# 8Bit_audio_-_7524_axelb.net
KiCad netlist of a schematic drawn in EAGLE
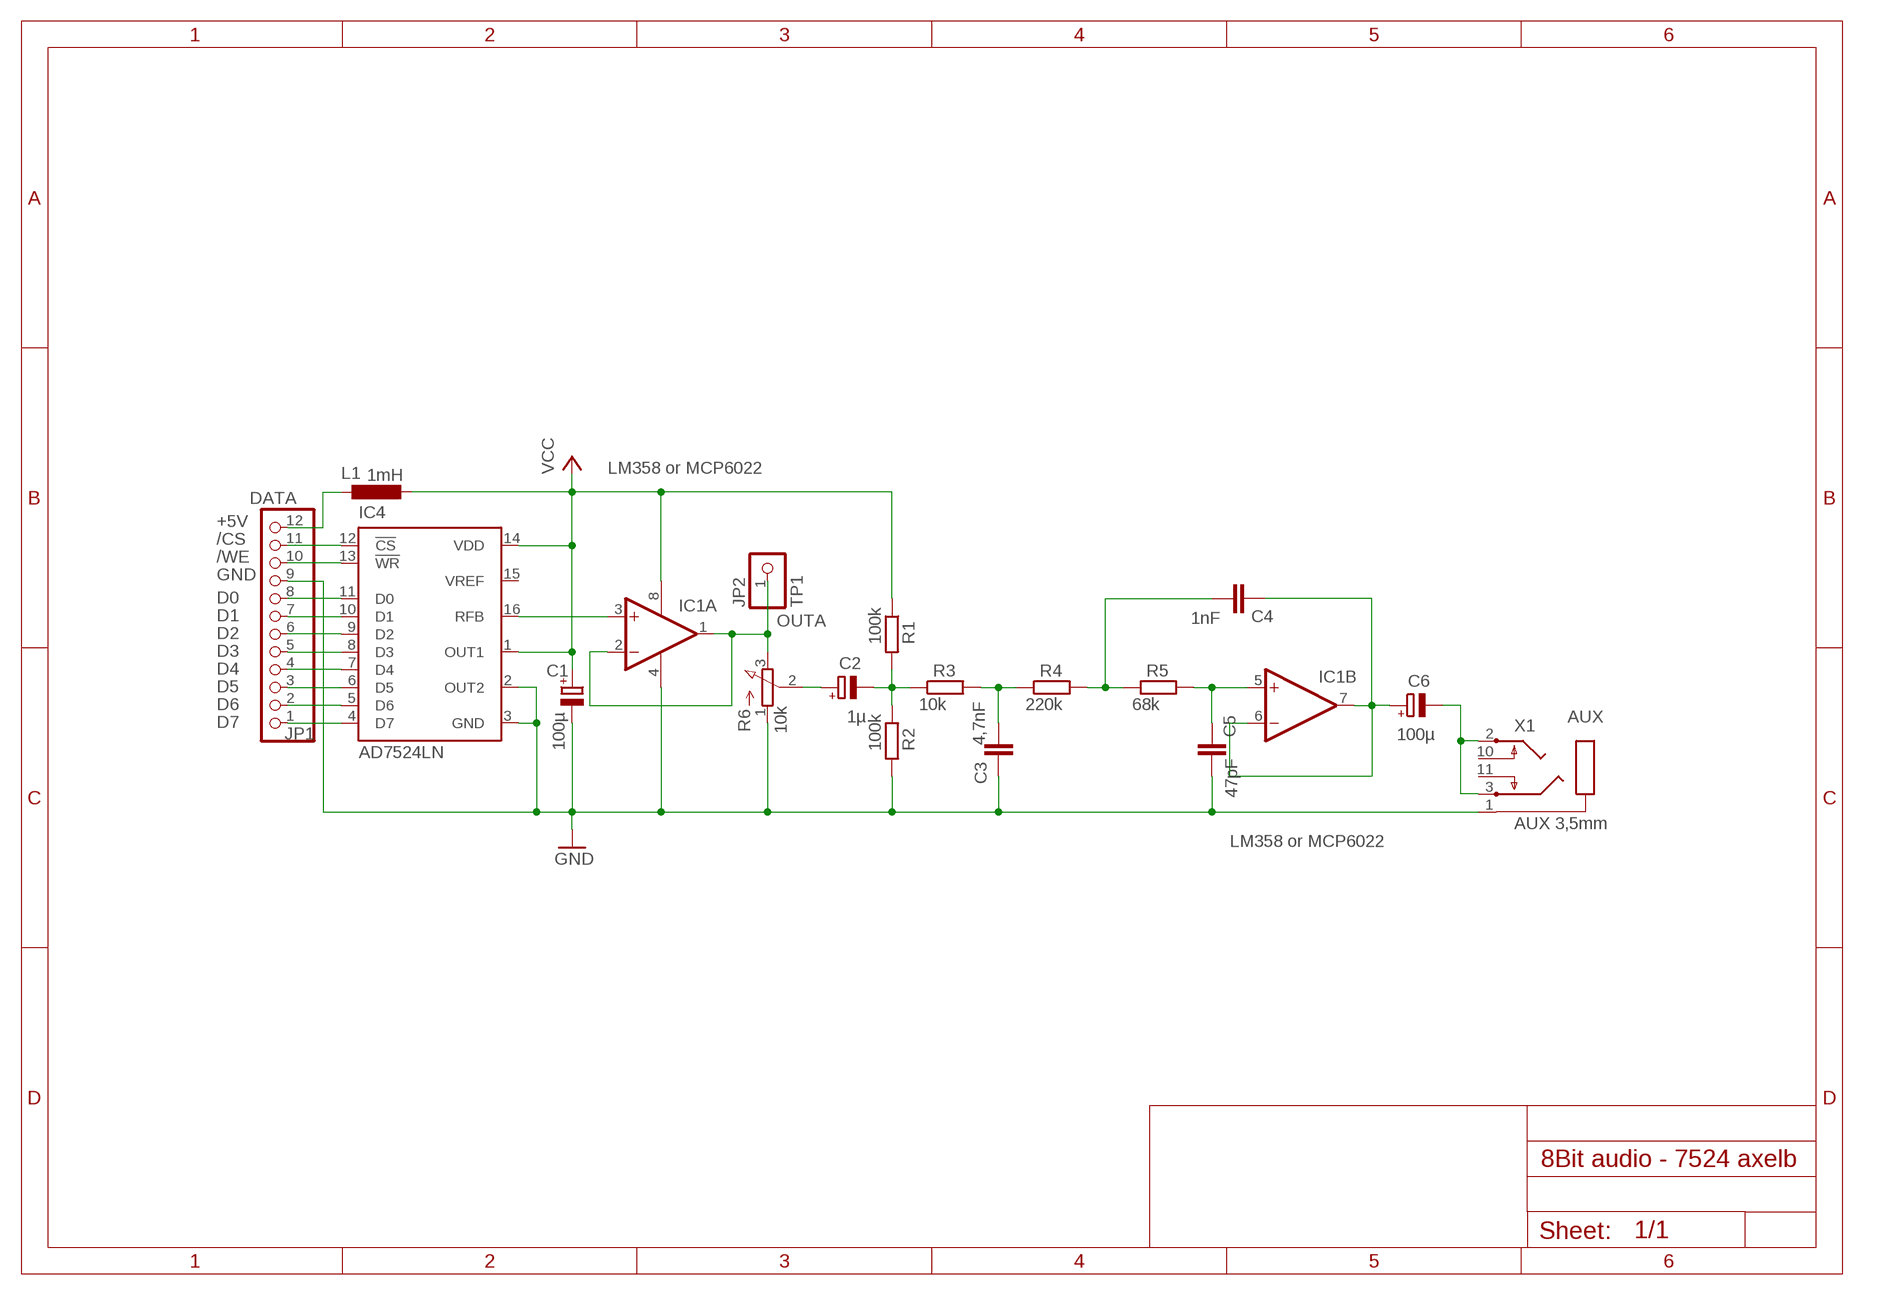
[diagram p0: schematic, sheet 1]

(export (version "E")
  (design (tool "Eeschema 10.0.6"))
  (components
    (comp (ref "C1")
      (value "100µ")
      (footprint "eagle-import:E5-5")
      (libsource (lib "eagle-import") (part "CPOL-EUE5-5"))
    )
    (comp (ref "C2")
      (value "1µ")
      (footprint "eagle-import:E5-5")
      (libsource (lib "eagle-import") (part "CPOL-EUE5-5"))
    )
    (comp (ref "C3")
      (value "4,7nF")
      (footprint "eagle-import:C075-032X103")
      (libsource (lib "eagle-import") (part "C-EU075-032X103"))
    )
    (comp (ref "C4")
      (value "1nF")
      (footprint "eagle-import:C075-032X103")
      (libsource (lib "eagle-import") (part "C-EU075-032X103"))
    )
    (comp (ref "C5")
      (value "47pF")
      (footprint "eagle-import:C075-032X103")
      (libsource (lib "eagle-import") (part "C-EU075-032X103"))
    )
    (comp (ref "C6")
      (value "100µ")
      (footprint "eagle-import:E5-5")
      (libsource (lib "eagle-import") (part "CPOL-EUE5-5"))
    )
    (comp (ref "IC1")
      (value "LM358 or MCP6022")
      (footprint "eagle-import:DIL08")
      (libsource (lib "eagle-import") (part "LM358N"))
    )
    (comp (ref "IC4")
      (value "AD7524LN")
      (footprint "eagle-import:DIL16")
      (fields (field (name "MF") "ALTERA CORPORATION") (field (name "MPN") "AD7524LNZ"))
      (libsource (lib "eagle-import") (part "AD7524NL"))
    )
    (comp (ref "JP1")
      (value "DATA")
      (footprint "eagle-import:1X12")
      (libsource (lib "eagle-import") (part "PINHD-1X12"))
    )
    (comp (ref "JP2")
      (value "TP1")
      (footprint "eagle-import:1X01")
      (libsource (lib "eagle-import") (part "PINHD-1X1"))
    )
    (comp (ref "L1")
      (value "1mH")
      (footprint "eagle-import:0207_10")
      (libsource (lib "eagle-import") (part "L-EU0207/10"))
    )
    (comp (ref "R1")
      (value "100k")
      (footprint "eagle-import:0207_10")
      (libsource (lib "eagle-import") (part "R-EU_0207/10"))
    )
    (comp (ref "R2")
      (value "100k")
      (footprint "eagle-import:0207_10")
      (libsource (lib "eagle-import") (part "R-EU_0207/10"))
    )
    (comp (ref "R3")
      (value "10k")
      (footprint "eagle-import:0207_10")
      (libsource (lib "eagle-import") (part "R-EU_0207/10"))
    )
    (comp (ref "R4")
      (value "220k")
      (footprint "eagle-import:0207_10")
      (libsource (lib "eagle-import") (part "R-EU_0207/10"))
    )
    (comp (ref "R5")
      (value "68k")
      (footprint "eagle-import:0207_10")
      (libsource (lib "eagle-import") (part "R-EU_0207/10"))
    )
    (comp (ref "R6")
      (value "10k")
      (footprint "eagle-import:3RP_1610N")
      (libsource (lib "eagle-import") (part "3RP/1610N"))
    )
    (comp (ref "X1")
      (value "AUX 3,5mm")
      (footprint "eagle-import:SJ1-352XN")
      (libsource (lib "eagle-import") (part "CON-SJ1-352XNSJ1-352XN"))
    )
  )
  (nets
    (net (code "1") (name "/+5V") (class "Default")
      (node (ref "JP1") (pin "12") (pinfunction "12_12") (pintype "passive"))
      (node (ref "L1") (pin "1") (pinfunction "1_1") (pintype "passive"))
    )
    (net (code "2") (name "/AUX") (class "Default")
      (node (ref "C6") (pin "-") (pinfunction "-_-") (pintype "passive"))
      (node (ref "X1") (pin "2") (pinfunction "2_2") (pintype "passive"))
      (node (ref "X1") (pin "3") (pinfunction "3_3") (pintype "passive"))
    )
    (net (code "3") (name "/D0") (class "Default")
      (node (ref "IC4") (pin "11") (pinfunction "D0_11") (pintype "input"))
      (node (ref "JP1") (pin "8") (pinfunction "8_8") (pintype "passive"))
    )
    (net (code "4") (name "/D1") (class "Default")
      (node (ref "IC4") (pin "10") (pinfunction "D1_10") (pintype "input"))
      (node (ref "JP1") (pin "7") (pinfunction "7_7") (pintype "passive"))
    )
    (net (code "5") (name "/D2") (class "Default")
      (node (ref "IC4") (pin "9") (pinfunction "D2_9") (pintype "input"))
      (node (ref "JP1") (pin "6") (pinfunction "6_6") (pintype "passive"))
    )
    (net (code "6") (name "/D3") (class "Default")
      (node (ref "IC4") (pin "8") (pinfunction "D3_8") (pintype "input"))
      (node (ref "JP1") (pin "5") (pinfunction "5_5") (pintype "passive"))
    )
    (net (code "7") (name "/D4") (class "Default")
      (node (ref "IC4") (pin "7") (pinfunction "D4_7") (pintype "input"))
      (node (ref "JP1") (pin "4") (pinfunction "4_4") (pintype "passive"))
    )
    (net (code "8") (name "/D5") (class "Default")
      (node (ref "IC4") (pin "6") (pinfunction "D5_6") (pintype "input"))
      (node (ref "JP1") (pin "3") (pinfunction "3_3") (pintype "passive"))
    )
    (net (code "9") (name "/D6") (class "Default")
      (node (ref "IC4") (pin "5") (pinfunction "D6_5") (pintype "input"))
      (node (ref "JP1") (pin "2") (pinfunction "2_2") (pintype "passive"))
    )
    (net (code "10") (name "/D7") (class "Default")
      (node (ref "IC4") (pin "4") (pinfunction "D7_4") (pintype "input"))
      (node (ref "JP1") (pin "1") (pinfunction "1_1") (pintype "passive"))
    )
    (net (code "11") (name "/OUTA") (class "Default")
      (node (ref "IC1") (pin "1") (pinfunction "OUT_1") (pintype "output"))
      (node (ref "IC1") (pin "2") (pinfunction "-IN_2") (pintype "input"))
      (node (ref "JP2") (pin "1") (pinfunction "1_1") (pintype "passive"))
      (node (ref "R6") (pin "3") (pinfunction "E_3") (pintype "passive"))
    )
    (net (code "12") (name "/{slash}CS") (class "Default")
      (node (ref "IC4") (pin "12") (pinfunction "~{CS}_12") (pintype "input"))
      (node (ref "JP1") (pin "11") (pinfunction "11_11") (pintype "passive"))
    )
    (net (code "13") (name "/{slash}WE") (class "Default")
      (node (ref "IC4") (pin "13") (pinfunction "~{WR}_13") (pintype "input"))
      (node (ref "JP1") (pin "10") (pinfunction "10_10") (pintype "passive"))
    )
    (net (code "14") (name "GND") (class "Default")
      (node (ref "C1") (pin "-") (pinfunction "-_-") (pintype "passive"))
      (node (ref "C3") (pin "1") (pinfunction "1_1") (pintype "passive"))
      (node (ref "C5") (pin "2") (pinfunction "2_2") (pintype "passive"))
      (node (ref "IC1") (pin "4") (pinfunction "V-_4") (pintype "power_in"))
      (node (ref "IC4") (pin "2") (pinfunction "OUT2_2") (pintype "passive"))
      (node (ref "IC4") (pin "3") (pinfunction "GND_3") (pintype "power_in"))
      (node (ref "JP1") (pin "9") (pinfunction "9_9") (pintype "passive"))
      (node (ref "R2") (pin "2") (pinfunction "2_2") (pintype "passive"))
      (node (ref "R6") (pin "1") (pinfunction "A_1") (pintype "passive"))
      (node (ref "X1") (pin "1") (pinfunction "1_1") (pintype "passive"))
    )
    (net (code "15") (name "Net-(C2-Pad-)") (class "Default")
      (node (ref "C2") (pin "-") (pinfunction "-_-") (pintype "passive"))
      (node (ref "R1") (pin "2") (pinfunction "2_2") (pintype "passive"))
      (node (ref "R2") (pin "1") (pinfunction "1_1") (pintype "passive"))
      (node (ref "R3") (pin "1") (pinfunction "1_1") (pintype "passive"))
    )
    (net (code "16") (name "Net-(C3-Pad2)") (class "Default")
      (node (ref "C3") (pin "2") (pinfunction "2_2") (pintype "passive"))
      (node (ref "R3") (pin "2") (pinfunction "2_2") (pintype "passive"))
      (node (ref "R4") (pin "1") (pinfunction "1_1") (pintype "passive"))
    )
    (net (code "17") (name "Net-(C4-Pad2)") (class "Default")
      (node (ref "C4") (pin "2") (pinfunction "2_2") (pintype "passive"))
      (node (ref "R4") (pin "2") (pinfunction "2_2") (pintype "passive"))
      (node (ref "R5") (pin "1") (pinfunction "1_1") (pintype "passive"))
    )
    (net (code "18") (name "Net-(IC1A-+IN)") (class "Default")
      (node (ref "IC1") (pin "3") (pinfunction "+IN_3") (pintype "input"))
      (node (ref "IC4") (pin "16") (pinfunction "RFB_16") (pintype "passive"))
    )
    (net (code "19") (name "Net-(IC1B-+IN)") (class "Default")
      (node (ref "C5") (pin "1") (pinfunction "1_1") (pintype "passive"))
      (node (ref "IC1") (pin "5") (pinfunction "+IN_5") (pintype "input"))
      (node (ref "R5") (pin "2") (pinfunction "2_2") (pintype "passive"))
    )
    (net (code "20") (name "Net-(IC1B--IN)") (class "Default")
      (node (ref "C4") (pin "1") (pinfunction "1_1") (pintype "passive"))
      (node (ref "C6") (pin "+") (pinfunction "+_+") (pintype "passive"))
      (node (ref "IC1") (pin "6") (pinfunction "-IN_6") (pintype "input"))
      (node (ref "IC1") (pin "7") (pinfunction "OUT_7") (pintype "output"))
    )
    (net (code "21") (name "Net-(R6-S)") (class "Default")
      (node (ref "C2") (pin "+") (pinfunction "+_+") (pintype "passive"))
      (node (ref "R6") (pin "2") (pinfunction "S_2") (pintype "passive"))
    )
    (net (code "22") (name "VCC") (class "Default")
      (node (ref "C1") (pin "+") (pinfunction "+_+") (pintype "passive"))
      (node (ref "IC1") (pin "8") (pinfunction "V+_8") (pintype "power_in"))
      (node (ref "IC4") (pin "1") (pinfunction "OUT1_1") (pintype "passive"))
      (node (ref "IC4") (pin "14") (pinfunction "VDD_14") (pintype "power_in"))
      (node (ref "L1") (pin "2") (pinfunction "2_2") (pintype "passive"))
      (node (ref "R1") (pin "1") (pinfunction "1_1") (pintype "passive"))
    )
    (net (code "23") (name "unconnected-(IC4-VREF-Pad15)") (class "Default")
      (node (ref "IC4") (pin "15") (pinfunction "VREF_15") (pintype "input"))
    )
    (net (code "24") (name "unconnected-(X1-Pad10)") (class "Default")
      (node (ref "X1") (pin "10") (pinfunction "10_10") (pintype "passive"))
    )
    (net (code "25") (name "unconnected-(X1-Pad11)") (class "Default")
      (node (ref "X1") (pin "11") (pinfunction "11_11") (pintype "passive"))
    )
  )
)
